# HH-08MX.net
KiCad netlist of a schematic drawn in EAGLE
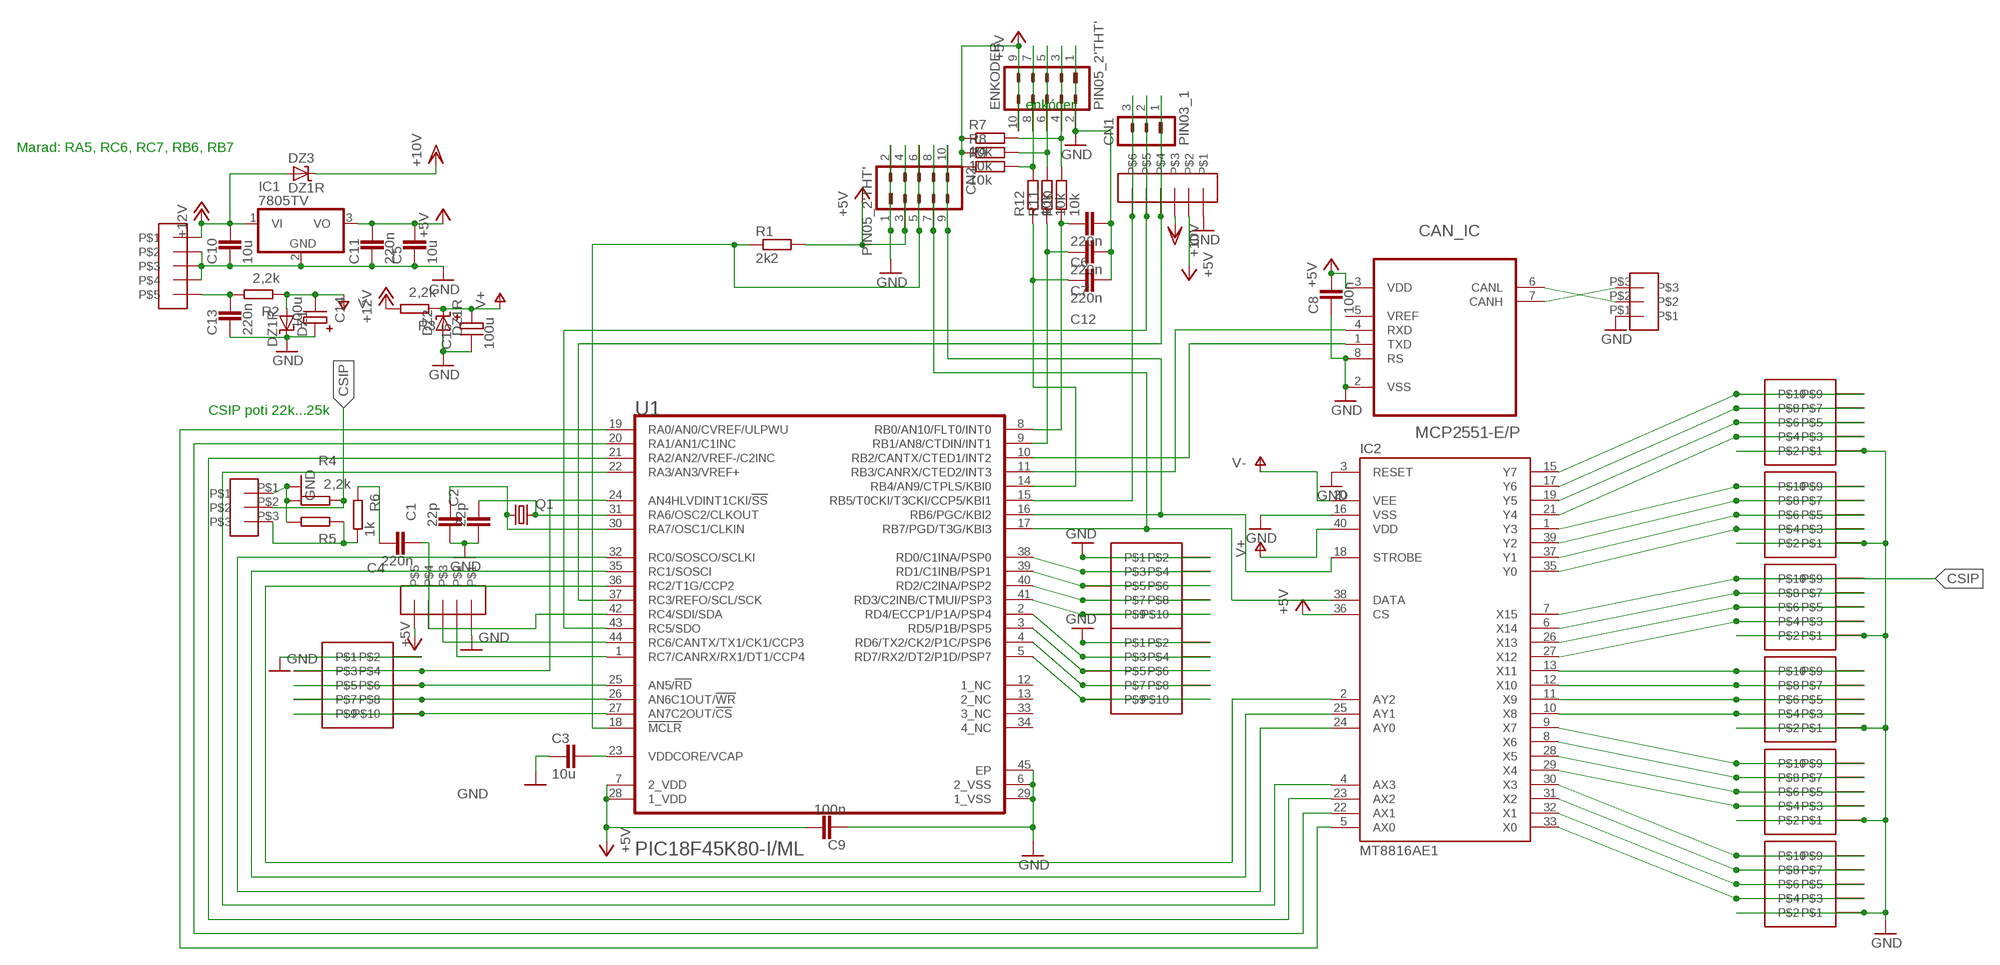
[diagram p0: schematic, sheet 1]

(export (version "E")
  (design (tool "Eeschema 10.0.6"))
  (components
    (comp (ref "BE1-4")
      (value "KERETES_TUS_10")
      (footprint "eagle-import:KERETES_TUS_10")
      (libsource (lib "eagle-import") (part "KERETES_TUS_10"))
    )
    (comp (ref "BE5-8")
      (value "KERETES_TUS_10")
      (footprint "eagle-import:KERETES_TUS_10")
      (libsource (lib "eagle-import") (part "KERETES_TUS_10"))
    )
    (comp (ref "BE9-12")
      (value "KERETES_TUS_10")
      (footprint "eagle-import:KERETES_TUS_10")
      (libsource (lib "eagle-import") (part "KERETES_TUS_10"))
    )
    (comp (ref "BE13-16")
      (value "KERETES_TUS_10")
      (footprint "eagle-import:KERETES_TUS_10")
      (libsource (lib "eagle-import") (part "KERETES_TUS_10"))
    )
    (comp (ref "C1")
      (value "22p")
      (footprint "eagle-import:R_0805_NAGY")
      (libsource (lib "eagle-import") (part "C0805_NAGY"))
    )
    (comp (ref "C2")
      (value "22p")
      (footprint "eagle-import:R_0805_NAGY")
      (libsource (lib "eagle-import") (part "C0805_NAGY"))
    )
    (comp (ref "C3")
      (value "10u")
      (footprint "eagle-import:R_0805_NAGY")
      (libsource (lib "eagle-import") (part "C0805_NAGY"))
    )
    (comp (ref "C4")
      (value "220n")
      (footprint "eagle-import:R_0805_NAGY")
      (libsource (lib "eagle-import") (part "C0805_NAGY"))
    )
    (comp (ref "C5")
      (value "10u")
      (footprint "eagle-import:R_0805_NAGY")
      (libsource (lib "eagle-import") (part "C0805_NAGY"))
    )
    (comp (ref "C6")
      (value "220n")
      (footprint "eagle-import:R_0805_NAGY")
      (libsource (lib "eagle-import") (part "C0805_NAGY"))
    )
    (comp (ref "C7")
      (value "220n")
      (footprint "eagle-import:R_0805_NAGY")
      (libsource (lib "eagle-import") (part "C0805_NAGY"))
    )
    (comp (ref "C8")
      (value "100n")
      (footprint "eagle-import:R_0805_NAGY")
      (libsource (lib "eagle-import") (part "C0805_NAGY"))
    )
    (comp (ref "C9")
      (value "100n")
      (footprint "eagle-import:R_0805_NAGY")
      (libsource (lib "eagle-import") (part "C0805_NAGY"))
    )
    (comp (ref "C10")
      (value "10u")
      (footprint "eagle-import:R_0805_NAGY")
      (libsource (lib "eagle-import") (part "C0805_NAGY"))
    )
    (comp (ref "C11")
      (value "220n")
      (footprint "eagle-import:R_0805_NAGY")
      (libsource (lib "eagle-import") (part "C0805_NAGY"))
    )
    (comp (ref "C12")
      (value "220n")
      (footprint "eagle-import:R_0805_NAGY")
      (libsource (lib "eagle-import") (part "C0805_NAGY"))
    )
    (comp (ref "C13")
      (value "220n")
      (footprint "eagle-import:R_0805_NAGY")
      (libsource (lib "eagle-import") (part "C0805_NAGY"))
    )
    (comp (ref "C14")
      (value "100u")
      (footprint "eagle-import:C_EL1RASZT06")
      (libsource (lib "eagle-import") (part "C_EL1R06"))
    )
    (comp (ref "C15")
      (value "100u")
      (footprint "eagle-import:C_EL1RASZT06")
      (libsource (lib "eagle-import") (part "C_EL1R06"))
    )
    (comp (ref "CAN_IC")
      (value "MCP2551-E/P")
      (footprint "eagle-import:DIP254P762X432-8")
      (libsource (lib "eagle-import") (part "MCP2551-E/P"))
    )
    (comp (ref "CN1")
      (value "PIN03_1")
      (footprint "eagle-import:PIN03_1")
      (libsource (lib "eagle-import") (part "PIN03_1"))
    )
    (comp (ref "CN2")
      (value "PIN05_2'THT'")
      (footprint "eagle-import:PIN05_2")
      (libsource (lib "eagle-import") (part "PIN05_2'THT'"))
    )
    (comp (ref "DZ1")
      (value "DZ1R")
      (footprint "eagle-import:D1RASZT")
      (libsource (lib "eagle-import") (part "DZ1R"))
    )
    (comp (ref "DZ2")
      (value "DZ1R")
      (footprint "eagle-import:D1RASZT")
      (libsource (lib "eagle-import") (part "DZ1R"))
    )
    (comp (ref "DZ3")
      (value "DZ1R")
      (footprint "eagle-import:D1RASZT")
      (libsource (lib "eagle-import") (part "DZ1R"))
    )
    (comp (ref "ENKODER")
      (value "PIN05_2'THT'")
      (footprint "eagle-import:PIN05_2")
      (libsource (lib "eagle-import") (part "PIN05_2'THT'"))
    )
    (comp (ref "IC1")
      (value "7805TV")
      (footprint "eagle-import:TO220V")
      (libsource (lib "eagle-import") (part "78TV05"))
    )
    (comp (ref "IC2")
      (value "MT8816AE1")
      (footprint "eagle-import:DIL40")
      (libsource (lib "eagle-import") (part "MT8816AE1"))
    )
    (comp (ref "KI1-4")
      (value "KERETES_TUS_10")
      (footprint "eagle-import:KERETES_TUS_10")
      (libsource (lib "eagle-import") (part "KERETES_TUS_10"))
    )
    (comp (ref "KI5-8")
      (value "KERETES_TUS_10")
      (footprint "eagle-import:KERETES_TUS_10")
      (libsource (lib "eagle-import") (part "KERETES_TUS_10"))
    )
    (comp (ref "KIJELZO")
      (value "FEHER_TUS_6")
      (footprint "eagle-import:FEHER_TUS_6")
      (libsource (lib "eagle-import") (part "FEHER_TUS_6"))
    )
    (comp (ref "Q1")
      (value "XTAL_2QS")
      (footprint "eagle-import:XTAL_QS")
      (libsource (lib "eagle-import") (part "XTAL_2QS"))
    )
    (comp (ref "R1")
      (value "2k2")
      (footprint "eagle-import:R0805")
      (libsource (lib "eagle-import") (part "R-EU_R0805"))
    )
    (comp (ref "R2")
      (value "2,2k")
      (footprint "eagle-import:R_0805_NAGY")
      (libsource (lib "eagle-import") (part "R_EU0805_NAGY"))
    )
    (comp (ref "R3")
      (value "2,2k")
      (footprint "eagle-import:R_0805_NAGY")
      (libsource (lib "eagle-import") (part "R_EU0805_NAGY"))
    )
    (comp (ref "R4")
      (value "2,2k")
      (footprint "eagle-import:R_0805_NAGY")
      (libsource (lib "eagle-import") (part "R_EU0805_NAGY"))
    )
    (comp (ref "R5")
      (value "R_EU0805_NAGY")
      (footprint "eagle-import:R_0805_NAGY")
      (libsource (lib "eagle-import") (part "R_EU0805_NAGY"))
    )
    (comp (ref "R6")
      (value "1k")
      (footprint "eagle-import:R_0805_NAGY")
      (libsource (lib "eagle-import") (part "R_EU0805_NAGY"))
    )
    (comp (ref "R7")
      (value "10k")
      (footprint "eagle-import:R0805")
      (libsource (lib "eagle-import") (part "R-EU_R0805"))
    )
    (comp (ref "R8")
      (value "10k")
      (footprint "eagle-import:R0805")
      (libsource (lib "eagle-import") (part "R-EU_R0805"))
    )
    (comp (ref "R9")
      (value "10k")
      (footprint "eagle-import:R0805")
      (libsource (lib "eagle-import") (part "R-EU_R0805"))
    )
    (comp (ref "R10")
      (value "10k")
      (footprint "eagle-import:R0805")
      (libsource (lib "eagle-import") (part "R-EU_R0805"))
    )
    (comp (ref "R11")
      (value "10k")
      (footprint "eagle-import:R0805")
      (libsource (lib "eagle-import") (part "R-EU_R0805"))
    )
    (comp (ref "R12")
      (value "10k")
      (footprint "eagle-import:R0805")
      (libsource (lib "eagle-import") (part "R-EU_R0805"))
    )
    (comp (ref "SOROSPORT")
      (value "FEHER_TUS_5")
      (footprint "eagle-import:FEHER_TUS_5")
      (libsource (lib "eagle-import") (part "FEHER_TUS_5"))
    )
    (comp (ref "U$1")
      (value "FEHER_TUS_3")
      (footprint "eagle-import:FEHER_TUS_3")
      (libsource (lib "eagle-import") (part "FEHER_TUS_3"))
    )
    (comp (ref "U$4")
      (value "FEHER_TUS_3")
      (footprint "eagle-import:FEHER_TUS_3")
      (libsource (lib "eagle-import") (part "FEHER_TUS_3"))
    )
    (comp (ref "U$5")
      (value "FEHER_TUS_5")
      (footprint "eagle-import:FEHER_TUS_5")
      (libsource (lib "eagle-import") (part "FEHER_TUS_5"))
    )
    (comp (ref "U$14")
      (value "KERETES_TUS_10")
      (footprint "eagle-import:KERETES_TUS_10")
      (libsource (lib "eagle-import") (part "KERETES_TUS_10"))
    )
    (comp (ref "U$15")
      (value "KERETES_TUS_10")
      (footprint "eagle-import:KERETES_TUS_10")
      (libsource (lib "eagle-import") (part "KERETES_TUS_10"))
    )
    (comp (ref "U$16")
      (value "KERETES_TUS_10")
      (footprint "eagle-import:KERETES_TUS_10")
      (libsource (lib "eagle-import") (part "KERETES_TUS_10"))
    )
    (comp (ref "U1")
      (value "MICROCHIP_PIC18F45K80-I-MLMICROCHIP_PIC18F45K80-I-ML_0_2")
      (footprint "eagle-import:MICROCHIP_PIC18F45K80-I-ML_2")
      (fields (field (name "MF") "Microchip") (field (name "MPN") "PIC18F45K80-I/ML"))
      (libsource (lib "eagle-import") (part "MICROCHIP_PIC18F45K80-I-MLMICROCHIP_PIC18F45K80-I-ML_0_2"))
    )
  )
  (nets
    (net (code "1") (name "+5V") (class "Default")
      (node (ref "C11") (pin "1") (pinfunction "1_1") (pintype "passive"))
      (node (ref "C5") (pin "1") (pinfunction "1_1") (pintype "passive"))
      (node (ref "C8") (pin "1") (pinfunction "1_1") (pintype "passive"))
      (node (ref "C9") (pin "1") (pinfunction "1_1") (pintype "passive"))
      (node (ref "CAN_IC") (pin "3") (pinfunction "VDD_3") (pintype "power_in"))
      (node (ref "CN2") (pin "3") (pinfunction "3_3") (pintype "passive"))
      (node (ref "CN2") (pin "4") (pinfunction "4_4") (pintype "passive"))
      (node (ref "ENKODER") (pin "10") (pinfunction "10_10") (pintype "passive"))
      (node (ref "ENKODER") (pin "9") (pinfunction "9_9") (pintype "passive"))
      (node (ref "IC1") (pin "3") (pinfunction "VO_3") (pintype "passive"))
      (node (ref "IC2") (pin "36") (pinfunction "CS_36") (pintype "input"))
      (node (ref "KIJELZO") (pin "P$2") (pinfunction "P$2_P$2") (pintype "bidirectional"))
      (node (ref "R1") (pin "2") (pinfunction "2_2") (pintype "passive"))
      (node (ref "R7") (pin "1") (pinfunction "1_1") (pintype "passive"))
      (node (ref "R8") (pin "1") (pinfunction "1_1") (pintype "passive"))
      (node (ref "R9") (pin "1") (pinfunction "1_1") (pintype "passive"))
      (node (ref "SOROSPORT") (pin "P$5") (pinfunction "P$5_P$5") (pintype "bidirectional"))
      (node (ref "U1") (pin "28") (pinfunction "1_VDD_28") (pintype "power_in"))
      (node (ref "U1") (pin "7") (pinfunction "2_VDD_7") (pintype "power_in"))
    )
    (net (code "2") (name "+10V") (class "Default")
      (node (ref "DZ3") (pin "P$2") (pinfunction "C_P$2") (pintype "passive"))
      (node (ref "KIJELZO") (pin "P$3") (pinfunction "P$3_P$3") (pintype "bidirectional"))
    )
    (net (code "3") (name "+12V") (class "Default")
      (node (ref "C10") (pin "1") (pinfunction "1_1") (pintype "passive"))
      (node (ref "DZ3") (pin "P$1") (pinfunction "A_P$1") (pintype "passive"))
      (node (ref "IC1") (pin "1") (pinfunction "VI_1") (pintype "input"))
      (node (ref "R3") (pin "2") (pinfunction "E_2") (pintype "passive"))
      (node (ref "U$5") (pin "P$1") (pinfunction "P$1_P$1") (pintype "bidirectional"))
    )
    (net (code "4") (name "CSIP") (class "Default")
      (node (ref "BE13-16") (pin "P$10") (pinfunction "P$10_P$10") (pintype "bidirectional"))
      (node (ref "BE13-16") (pin "P$9") (pinfunction "P$9_P$9") (pintype "bidirectional"))
      (node (ref "IC2") (pin "7") (pinfunction "X15_7") (pintype "bidirectional"))
      (node (ref "R4") (pin "1") (pinfunction "A_1") (pintype "passive"))
      (node (ref "U$1") (pin "P$2") (pinfunction "P$2_P$2") (pintype "bidirectional"))
    )
    (net (code "5") (name "GND") (class "Default")
      (node (ref "BE1-4") (pin "P$1") (pinfunction "P$1_P$1") (pintype "bidirectional"))
      (node (ref "BE1-4") (pin "P$2") (pinfunction "P$2_P$2") (pintype "bidirectional"))
      (node (ref "BE13-16") (pin "P$1") (pinfunction "P$1_P$1") (pintype "bidirectional"))
      (node (ref "BE13-16") (pin "P$2") (pinfunction "P$2_P$2") (pintype "bidirectional"))
      (node (ref "BE5-8") (pin "P$1") (pinfunction "P$1_P$1") (pintype "bidirectional"))
      (node (ref "BE5-8") (pin "P$2") (pinfunction "P$2_P$2") (pintype "bidirectional"))
      (node (ref "BE9-12") (pin "P$1") (pinfunction "P$1_P$1") (pintype "bidirectional"))
      (node (ref "BE9-12") (pin "P$2") (pinfunction "P$2_P$2") (pintype "bidirectional"))
      (node (ref "C1") (pin "1") (pinfunction "1_1") (pintype "passive"))
      (node (ref "C10") (pin "2") (pinfunction "2_2") (pintype "passive"))
      (node (ref "C11") (pin "2") (pinfunction "2_2") (pintype "passive"))
      (node (ref "C12") (pin "1") (pinfunction "1_1") (pintype "passive"))
      (node (ref "C13") (pin "2") (pinfunction "2_2") (pintype "passive"))
      (node (ref "C14") (pin "P+") (pinfunction "P+_P+") (pintype "passive"))
      (node (ref "C15") (pin "P-") (pinfunction "P-_P-") (pintype "passive"))
      (node (ref "C2") (pin "1") (pinfunction "1_1") (pintype "passive"))
      (node (ref "C3") (pin "2") (pinfunction "2_2") (pintype "passive"))
      (node (ref "C5") (pin "2") (pinfunction "2_2") (pintype "passive"))
      (node (ref "C6") (pin "1") (pinfunction "1_1") (pintype "passive"))
      (node (ref "C7") (pin "1") (pinfunction "1_1") (pintype "passive"))
      (node (ref "C8") (pin "2") (pinfunction "2_2") (pintype "passive"))
      (node (ref "C9") (pin "2") (pinfunction "2_2") (pintype "passive"))
      (node (ref "CAN_IC") (pin "2") (pinfunction "VSS_2") (pintype "passive"))
      (node (ref "CAN_IC") (pin "8") (pinfunction "RS_8") (pintype "input"))
      (node (ref "CN2") (pin "1") (pinfunction "1_1") (pintype "passive"))
      (node (ref "CN2") (pin "2") (pinfunction "2_2") (pintype "passive"))
      (node (ref "DZ1") (pin "P$2") (pinfunction "C_P$2") (pintype "passive"))
      (node (ref "DZ2") (pin "P$1") (pinfunction "A_P$1") (pintype "passive"))
      (node (ref "ENKODER") (pin "1") (pinfunction "1_1") (pintype "passive"))
      (node (ref "ENKODER") (pin "2") (pinfunction "2_2") (pintype "passive"))
      (node (ref "IC1") (pin "2") (pinfunction "GND_2") (pintype "passive"))
      (node (ref "IC2") (pin "16") (pinfunction "VSS_16") (pintype "power_in"))
      (node (ref "IC2") (pin "3") (pinfunction "RESET_3") (pintype "input"))
      (node (ref "KI1-4") (pin "P$1") (pinfunction "P$1_P$1") (pintype "bidirectional"))
      (node (ref "KI1-4") (pin "P$2") (pinfunction "P$2_P$2") (pintype "bidirectional"))
      (node (ref "KI5-8") (pin "P$1") (pinfunction "P$1_P$1") (pintype "bidirectional"))
      (node (ref "KI5-8") (pin "P$2") (pinfunction "P$2_P$2") (pintype "bidirectional"))
      (node (ref "KIJELZO") (pin "P$1") (pinfunction "P$1_P$1") (pintype "bidirectional"))
      (node (ref "R4") (pin "2") (pinfunction "E_2") (pintype "passive"))
      (node (ref "R5") (pin "2") (pinfunction "E_2") (pintype "passive"))
      (node (ref "SOROSPORT") (pin "P$1") (pinfunction "P$1_P$1") (pintype "bidirectional"))
      (node (ref "U$1") (pin "P$1") (pinfunction "P$1_P$1") (pintype "bidirectional"))
      (node (ref "U$14") (pin "P$1") (pinfunction "P$1_P$1") (pintype "bidirectional"))
      (node (ref "U$14") (pin "P$2") (pinfunction "P$2_P$2") (pintype "bidirectional"))
      (node (ref "U$15") (pin "P$1") (pinfunction "P$1_P$1") (pintype "bidirectional"))
      (node (ref "U$15") (pin "P$2") (pinfunction "P$2_P$2") (pintype "bidirectional"))
      (node (ref "U$16") (pin "P$1") (pinfunction "P$1_P$1") (pintype "bidirectional"))
      (node (ref "U$16") (pin "P$2") (pinfunction "P$2_P$2") (pintype "bidirectional"))
      (node (ref "U$4") (pin "P$1") (pinfunction "P$1_P$1") (pintype "bidirectional"))
      (node (ref "U$5") (pin "P$2") (pinfunction "P$2_P$2") (pintype "bidirectional"))
      (node (ref "U$5") (pin "P$3") (pinfunction "P$3_P$3") (pintype "bidirectional"))
      (node (ref "U$5") (pin "P$4") (pinfunction "P$4_P$4") (pintype "bidirectional"))
      (node (ref "U1") (pin "29") (pinfunction "1_VSS_29") (pintype "power_in"))
      (node (ref "U1") (pin "45") (pinfunction "EP_45") (pintype "power_in"))
      (node (ref "U1") (pin "6") (pinfunction "2_VSS_6") (pintype "power_in"))
    )
    (net (code "6") (name "Net-(CAN_IC-CANH)") (class "Default")
      (node (ref "CAN_IC") (pin "7") (pinfunction "CANH_7") (pintype "output"))
      (node (ref "U$4") (pin "P$3") (pinfunction "P$3_P$3") (pintype "bidirectional"))
    )
    (net (code "7") (name "Net-(CAN_IC-CANL)") (class "Default")
      (node (ref "CAN_IC") (pin "6") (pinfunction "CANL_6") (pintype "output"))
      (node (ref "U$4") (pin "P$2") (pinfunction "P$2_P$2") (pintype "bidirectional"))
    )
    (net (code "8") (name "Net-(CAN_IC-RXD)") (class "Default")
      (node (ref "CAN_IC") (pin "4") (pinfunction "RXD_4") (pintype "input"))
      (node (ref "U1") (pin "11") (pinfunction "RB3/CANRX/CTED2/INT3_11") (pintype "bidirectional"))
    )
    (net (code "9") (name "Net-(CAN_IC-TXD)") (class "Default")
      (node (ref "CAN_IC") (pin "1") (pinfunction "TXD_1") (pintype "input"))
      (node (ref "U1") (pin "10") (pinfunction "RB2/CANTX/CTED1/INT2_10") (pintype "bidirectional"))
    )
    (net (code "10") (name "Net-(ENKODER-Pad3)") (class "Default")
      (node (ref "ENKODER") (pin "3") (pinfunction "3_3") (pintype "passive"))
      (node (ref "ENKODER") (pin "4") (pinfunction "4_4") (pintype "passive"))
      (node (ref "R10") (pin "2") (pinfunction "2_2") (pintype "passive"))
      (node (ref "R7") (pin "2") (pinfunction "2_2") (pintype "passive"))
    )
    (net (code "11") (name "Net-(ENKODER-Pad5)") (class "Default")
      (node (ref "ENKODER") (pin "5") (pinfunction "5_5") (pintype "passive"))
      (node (ref "ENKODER") (pin "6") (pinfunction "6_6") (pintype "passive"))
      (node (ref "R11") (pin "2") (pinfunction "2_2") (pintype "passive"))
      (node (ref "R8") (pin "2") (pinfunction "2_2") (pintype "passive"))
    )
    (net (code "12") (name "Net-(ENKODER-Pad7)") (class "Default")
      (node (ref "ENKODER") (pin "7") (pinfunction "7_7") (pintype "passive"))
      (node (ref "ENKODER") (pin "8") (pinfunction "8_8") (pintype "passive"))
      (node (ref "R12") (pin "2") (pinfunction "2_2") (pintype "passive"))
      (node (ref "R9") (pin "2") (pinfunction "2_2") (pintype "passive"))
    )
    (net (code "13") (name "Net-(IC2-AX0)") (class "Default")
      (node (ref "IC2") (pin "5") (pinfunction "AX0_5") (pintype "input"))
      (node (ref "U1") (pin "19") (pinfunction "RA0/AN0/CVREF/ULPWU_19") (pintype "bidirectional"))
    )
    (net (code "14") (name "Net-(IC2-AX1)") (class "Default")
      (node (ref "IC2") (pin "22") (pinfunction "AX1_22") (pintype "input"))
      (node (ref "U1") (pin "20") (pinfunction "RA1/AN1/C1INC_20") (pintype "bidirectional"))
    )
    (net (code "15") (name "Net-(IC2-AX2)") (class "Default")
      (node (ref "IC2") (pin "23") (pinfunction "AX2_23") (pintype "input"))
      (node (ref "U1") (pin "21") (pinfunction "RA2/AN2/VREF-/C2INC_21") (pintype "bidirectional"))
    )
    (net (code "16") (name "Net-(IC2-AX3)") (class "Default")
      (node (ref "IC2") (pin "4") (pinfunction "AX3_4") (pintype "input"))
      (node (ref "U1") (pin "22") (pinfunction "RA3/AN3/VREF+_22") (pintype "bidirectional"))
    )
    (net (code "17") (name "Net-(IC2-AY0)") (class "Default")
      (node (ref "IC2") (pin "24") (pinfunction "AY0_24") (pintype "input"))
      (node (ref "U1") (pin "32") (pinfunction "RC0/SOSCO/SCLKI_32") (pintype "bidirectional"))
    )
    (net (code "18") (name "Net-(IC2-AY1)") (class "Default")
      (node (ref "IC2") (pin "25") (pinfunction "AY1_25") (pintype "input"))
      (node (ref "U1") (pin "35") (pinfunction "RC1/SOSCI_35") (pintype "bidirectional"))
    )
    (net (code "19") (name "Net-(IC2-AY2)") (class "Default")
      (node (ref "IC2") (pin "2") (pinfunction "AY2_2") (pintype "input"))
      (node (ref "U1") (pin "36") (pinfunction "RC2/T1G/CCP2_36") (pintype "bidirectional"))
    )
    (net (code "20") (name "Net-(IC2-DATA)") (class "Default")
      (node (ref "CN2") (pin "7") (pinfunction "7_7") (pintype "passive"))
      (node (ref "CN2") (pin "8") (pinfunction "8_8") (pintype "passive"))
      (node (ref "IC2") (pin "38") (pinfunction "DATA_38") (pintype "input"))
      (node (ref "U1") (pin "17") (pinfunction "RB7/PGD/T3G/KBI3_17") (pintype "bidirectional"))
    )
    (net (code "21") (name "Net-(IC2-STROBE)") (class "Default")
      (node (ref "CN2") (pin "10") (pinfunction "10_10") (pintype "passive"))
      (node (ref "CN2") (pin "9") (pinfunction "9_9") (pintype "passive"))
      (node (ref "IC2") (pin "18") (pinfunction "STROBE_18") (pintype "input"))
      (node (ref "U1") (pin "16") (pinfunction "RB6/PGC/KBI2_16") (pintype "bidirectional"))
    )
    (net (code "22") (name "Net-(IC2-X0)") (class "Default")
      (node (ref "BE1-4") (pin "P$3") (pinfunction "P$3_P$3") (pintype "bidirectional"))
      (node (ref "BE1-4") (pin "P$4") (pinfunction "P$4_P$4") (pintype "bidirectional"))
      (node (ref "IC2") (pin "33") (pinfunction "X0_33") (pintype "bidirectional"))
    )
    (net (code "23") (name "Net-(IC2-X1)") (class "Default")
      (node (ref "BE1-4") (pin "P$5") (pinfunction "P$5_P$5") (pintype "bidirectional"))
      (node (ref "BE1-4") (pin "P$6") (pinfunction "P$6_P$6") (pintype "bidirectional"))
      (node (ref "IC2") (pin "32") (pinfunction "X1_32") (pintype "bidirectional"))
    )
    (net (code "24") (name "Net-(IC2-X2)") (class "Default")
      (node (ref "BE1-4") (pin "P$7") (pinfunction "P$7_P$7") (pintype "bidirectional"))
      (node (ref "BE1-4") (pin "P$8") (pinfunction "P$8_P$8") (pintype "bidirectional"))
      (node (ref "IC2") (pin "31") (pinfunction "X2_31") (pintype "bidirectional"))
    )
    (net (code "25") (name "Net-(IC2-X3)") (class "Default")
      (node (ref "BE1-4") (pin "P$10") (pinfunction "P$10_P$10") (pintype "bidirectional"))
      (node (ref "BE1-4") (pin "P$9") (pinfunction "P$9_P$9") (pintype "bidirectional"))
      (node (ref "IC2") (pin "30") (pinfunction "X3_30") (pintype "bidirectional"))
    )
    (net (code "26") (name "Net-(IC2-X4)") (class "Default")
      (node (ref "BE5-8") (pin "P$3") (pinfunction "P$3_P$3") (pintype "bidirectional"))
      (node (ref "BE5-8") (pin "P$4") (pinfunction "P$4_P$4") (pintype "bidirectional"))
      (node (ref "IC2") (pin "29") (pinfunction "X4_29") (pintype "bidirectional"))
    )
    (net (code "27") (name "Net-(IC2-X5)") (class "Default")
      (node (ref "BE5-8") (pin "P$5") (pinfunction "P$5_P$5") (pintype "bidirectional"))
      (node (ref "BE5-8") (pin "P$6") (pinfunction "P$6_P$6") (pintype "bidirectional"))
      (node (ref "IC2") (pin "28") (pinfunction "X5_28") (pintype "bidirectional"))
    )
    (net (code "28") (name "Net-(IC2-X6)") (class "Default")
      (node (ref "BE5-8") (pin "P$7") (pinfunction "P$7_P$7") (pintype "bidirectional"))
      (node (ref "BE5-8") (pin "P$8") (pinfunction "P$8_P$8") (pintype "bidirectional"))
      (node (ref "IC2") (pin "8") (pinfunction "X6_8") (pintype "bidirectional"))
    )
    (net (code "29") (name "Net-(IC2-X7)") (class "Default")
      (node (ref "BE5-8") (pin "P$10") (pinfunction "P$10_P$10") (pintype "bidirectional"))
      (node (ref "BE5-8") (pin "P$9") (pinfunction "P$9_P$9") (pintype "bidirectional"))
      (node (ref "IC2") (pin "9") (pinfunction "X7_9") (pintype "bidirectional"))
    )
    (net (code "30") (name "Net-(IC2-X8)") (class "Default")
      (node (ref "BE9-12") (pin "P$3") (pinfunction "P$3_P$3") (pintype "bidirectional"))
      (node (ref "BE9-12") (pin "P$4") (pinfunction "P$4_P$4") (pintype "bidirectional"))
      (node (ref "IC2") (pin "10") (pinfunction "X8_10") (pintype "bidirectional"))
    )
    (net (code "31") (name "Net-(IC2-X9)") (class "Default")
      (node (ref "BE9-12") (pin "P$5") (pinfunction "P$5_P$5") (pintype "bidirectional"))
      (node (ref "BE9-12") (pin "P$6") (pinfunction "P$6_P$6") (pintype "bidirectional"))
      (node (ref "IC2") (pin "11") (pinfunction "X9_11") (pintype "bidirectional"))
    )
    (net (code "32") (name "Net-(IC2-X10)") (class "Default")
      (node (ref "BE9-12") (pin "P$7") (pinfunction "P$7_P$7") (pintype "bidirectional"))
      (node (ref "BE9-12") (pin "P$8") (pinfunction "P$8_P$8") (pintype "bidirectional"))
      (node (ref "IC2") (pin "12") (pinfunction "X10_12") (pintype "bidirectional"))
    )
    (net (code "33") (name "Net-(IC2-X11)") (class "Default")
      (node (ref "BE9-12") (pin "P$10") (pinfunction "P$10_P$10") (pintype "bidirectional"))
      (node (ref "BE9-12") (pin "P$9") (pinfunction "P$9_P$9") (pintype "bidirectional"))
      (node (ref "IC2") (pin "13") (pinfunction "X11_13") (pintype "bidirectional"))
    )
    (net (code "34") (name "Net-(IC2-X12)") (class "Default")
      (node (ref "BE13-16") (pin "P$3") (pinfunction "P$3_P$3") (pintype "bidirectional"))
      (node (ref "BE13-16") (pin "P$4") (pinfunction "P$4_P$4") (pintype "bidirectional"))
      (node (ref "IC2") (pin "27") (pinfunction "X12_27") (pintype "bidirectional"))
    )
    (net (code "35") (name "Net-(IC2-X13)") (class "Default")
      (node (ref "BE13-16") (pin "P$5") (pinfunction "P$5_P$5") (pintype "bidirectional"))
      (node (ref "BE13-16") (pin "P$6") (pinfunction "P$6_P$6") (pintype "bidirectional"))
      (node (ref "IC2") (pin "26") (pinfunction "X13_26") (pintype "bidirectional"))
    )
    (net (code "36") (name "Net-(IC2-X14)") (class "Default")
      (node (ref "BE13-16") (pin "P$7") (pinfunction "P$7_P$7") (pintype "bidirectional"))
      (node (ref "BE13-16") (pin "P$8") (pinfunction "P$8_P$8") (pintype "bidirectional"))
      (node (ref "IC2") (pin "6") (pinfunction "X14_6") (pintype "bidirectional"))
    )
    (net (code "37") (name "Net-(IC2-Y0)") (class "Default")
      (node (ref "IC2") (pin "35") (pinfunction "Y0_35") (pintype "bidirectional"))
      (node (ref "KI1-4") (pin "P$3") (pinfunction "P$3_P$3") (pintype "bidirectional"))
      (node (ref "KI1-4") (pin "P$4") (pinfunction "P$4_P$4") (pintype "bidirectional"))
    )
    (net (code "38") (name "Net-(IC2-Y1)") (class "Default")
      (node (ref "IC2") (pin "37") (pinfunction "Y1_37") (pintype "bidirectional"))
      (node (ref "KI1-4") (pin "P$5") (pinfunction "P$5_P$5") (pintype "bidirectional"))
      (node (ref "KI1-4") (pin "P$6") (pinfunction "P$6_P$6") (pintype "bidirectional"))
    )
    (net (code "39") (name "Net-(IC2-Y2)") (class "Default")
      (node (ref "IC2") (pin "39") (pinfunction "Y2_39") (pintype "bidirectional"))
      (node (ref "KI1-4") (pin "P$7") (pinfunction "P$7_P$7") (pintype "bidirectional"))
      (node (ref "KI1-4") (pin "P$8") (pinfunction "P$8_P$8") (pintype "bidirectional"))
    )
    (net (code "40") (name "Net-(IC2-Y3)") (class "Default")
      (node (ref "IC2") (pin "1") (pinfunction "Y3_1") (pintype "bidirectional"))
      (node (ref "KI1-4") (pin "P$10") (pinfunction "P$10_P$10") (pintype "bidirectional"))
      (node (ref "KI1-4") (pin "P$9") (pinfunction "P$9_P$9") (pintype "bidirectional"))
    )
    (net (code "41") (name "Net-(IC2-Y4)") (class "Default")
      (node (ref "IC2") (pin "21") (pinfunction "Y4_21") (pintype "bidirectional"))
      (node (ref "KI5-8") (pin "P$3") (pinfunction "P$3_P$3") (pintype "bidirectional"))
      (node (ref "KI5-8") (pin "P$4") (pinfunction "P$4_P$4") (pintype "bidirectional"))
    )
    (net (code "42") (name "Net-(IC2-Y5)") (class "Default")
      (node (ref "IC2") (pin "19") (pinfunction "Y5_19") (pintype "bidirectional"))
      (node (ref "KI5-8") (pin "P$5") (pinfunction "P$5_P$5") (pintype "bidirectional"))
      (node (ref "KI5-8") (pin "P$6") (pinfunction "P$6_P$6") (pintype "bidirectional"))
    )
    (net (code "43") (name "Net-(IC2-Y6)") (class "Default")
      (node (ref "IC2") (pin "17") (pinfunction "Y6_17") (pintype "bidirectional"))
      (node (ref "KI5-8") (pin "P$7") (pinfunction "P$7_P$7") (pintype "bidirectional"))
      (node (ref "KI5-8") (pin "P$8") (pinfunction "P$8_P$8") (pintype "bidirectional"))
    )
    (net (code "44") (name "Net-(IC2-Y7)") (class "Default")
      (node (ref "IC2") (pin "15") (pinfunction "Y7_15") (pintype "bidirectional"))
      (node (ref "KI5-8") (pin "P$10") (pinfunction "P$10_P$10") (pintype "bidirectional"))
      (node (ref "KI5-8") (pin "P$9") (pinfunction "P$9_P$9") (pintype "bidirectional"))
    )
    (net (code "45") (name "Net-(R2-E)") (class "Default")
      (node (ref "C13") (pin "1") (pinfunction "1_1") (pintype "passive"))
      (node (ref "R2") (pin "2") (pinfunction "E_2") (pintype "passive"))
      (node (ref "U$5") (pin "P$5") (pinfunction "P$5_P$5") (pintype "bidirectional"))
    )
    (net (code "46") (name "Net-(R5-A)") (class "Default")
      (node (ref "R5") (pin "1") (pinfunction "A_1") (pintype "passive"))
      (node (ref "R6") (pin "2") (pinfunction "E_2") (pintype "passive"))
      (node (ref "U$1") (pin "P$3") (pinfunction "P$3_P$3") (pintype "bidirectional"))
    )
    (net (code "47") (name "Net-(R6-A)") (class "Default")
      (node (ref "C4") (pin "2") (pinfunction "2_2") (pintype "passive"))
      (node (ref "R6") (pin "1") (pinfunction "A_1") (pintype "passive"))
    )
    (net (code "48") (name "Net-(U1-AN4HLVDINT1CKI{slash}~{SS})") (class "Default")
      (node (ref "U$16") (pin "P$3") (pinfunction "P$3_P$3") (pintype "bidirectional"))
      (node (ref "U$16") (pin "P$4") (pinfunction "P$4_P$4") (pintype "bidirectional"))
      (node (ref "U1") (pin "24") (pinfunction "AN4HLVDINT1CKI/~{SS}_24") (pintype "bidirectional"))
    )
    (net (code "49") (name "Net-(U1-AN5{slash}~{RD})") (class "Default")
      (node (ref "U$16") (pin "P$5") (pinfunction "P$5_P$5") (pintype "bidirectional"))
      (node (ref "U$16") (pin "P$6") (pinfunction "P$6_P$6") (pintype "bidirectional"))
      (node (ref "U1") (pin "25") (pinfunction "AN5/~{RD}_25") (pintype "bidirectional"))
    )
    (net (code "50") (name "Net-(U1-AN6C1OUT{slash}~{WR})") (class "Default")
      (node (ref "U$16") (pin "P$7") (pinfunction "P$7_P$7") (pintype "bidirectional"))
      (node (ref "U$16") (pin "P$8") (pinfunction "P$8_P$8") (pintype "bidirectional"))
      (node (ref "U1") (pin "26") (pinfunction "AN6C1OUT/~{WR}_26") (pintype "bidirectional"))
    )
    (net (code "51") (name "Net-(U1-AN7C2OUT{slash}~{CS})") (class "Default")
      (node (ref "U$16") (pin "P$10") (pinfunction "P$10_P$10") (pintype "bidirectional"))
      (node (ref "U$16") (pin "P$9") (pinfunction "P$9_P$9") (pintype "bidirectional"))
      (node (ref "U1") (pin "27") (pinfunction "AN7C2OUT/~{CS}_27") (pintype "bidirectional"))
    )
    (net (code "52") (name "Net-(U1-RA6{slash}OSC2{slash}CLKOUT)") (class "Default")
      (node (ref "C2") (pin "2") (pinfunction "2_2") (pintype "passive"))
      (node (ref "Q1") (pin "2") (pinfunction "2_2") (pintype "passive"))
      (node (ref "U1") (pin "31") (pinfunction "RA6/OSC2/CLKOUT_31") (pintype "bidirectional"))
    )
    (net (code "53") (name "Net-(U1-RA7{slash}OSC1{slash}CLKIN)") (class "Default")
      (node (ref "C1") (pin "2") (pinfunction "2_2") (pintype "passive"))
      (node (ref "Q1") (pin "1") (pinfunction "1_1") (pintype "passive"))
      (node (ref "U1") (pin "30") (pinfunction "RA7/OSC1/CLKIN_30") (pintype "bidirectional"))
    )
    (net (code "54") (name "Net-(U1-RB0{slash}AN10{slash}FLT0{slash}INT0)") (class "Default")
      (node (ref "C6") (pin "2") (pinfunction "2_2") (pintype "passive"))
      (node (ref "R10") (pin "1") (pinfunction "1_1") (pintype "passive"))
      (node (ref "U1") (pin "8") (pinfunction "RB0/AN10/FLT0/INT0_8") (pintype "bidirectional"))
    )
    (net (code "55") (name "Net-(U1-RB1{slash}AN8{slash}CTDIN{slash}INT1)") (class "Default")
      (node (ref "C7") (pin "2") (pinfunction "2_2") (pintype "passive"))
      (node (ref "R11") (pin "1") (pinfunction "1_1") (pintype "passive"))
      (node (ref "U1") (pin "9") (pinfunction "RB1/AN8/CTDIN/INT1_9") (pintype "bidirectional"))
    )
    (net (code "56") (name "Net-(U1-RB4{slash}AN9{slash}CTPLS{slash}KBI0)") (class "Default")
      (node (ref "C12") (pin "2") (pinfunction "2_2") (pintype "passive"))
      (node (ref "R12") (pin "1") (pinfunction "1_1") (pintype "passive"))
      (node (ref "U1") (pin "14") (pinfunction "RB4/AN9/CTPLS/KBI0_14") (pintype "bidirectional"))
    )
    (net (code "57") (name "Net-(U1-RB5{slash}T0CKI{slash}T3CKI{slash}CCP5{slash}KBI1)") (class "Default")
      (node (ref "CN1") (pin "3") (pinfunction "3_3") (pintype "passive"))
      (node (ref "KIJELZO") (pin "P$6") (pinfunction "P$6_P$6") (pintype "bidirectional"))
      (node (ref "U1") (pin "15") (pinfunction "RB5/T0CKI/T3CKI/CCP5/KBI1_15") (pintype "bidirectional"))
    )
    (net (code "58") (name "Net-(U1-RC3{slash}REFO{slash}SCL{slash}SCK)") (class "Default")
      (node (ref "CN1") (pin "1") (pinfunction "1_1") (pintype "passive"))
      (node (ref "KIJELZO") (pin "P$4") (pinfunction "P$4_P$4") (pintype "bidirectional"))
      (node (ref "U1") (pin "37") (pinfunction "RC3/REFO/SCL/SCK_37") (pintype "bidirectional"))
    )
    (net (code "59") (name "Net-(U1-RC4{slash}SDI{slash}SDA)") (class "Default")
      (node (ref "C4") (pin "1") (pinfunction "1_1") (pintype "passive"))
      (node (ref "SOROSPORT") (pin "P$4") (pinfunction "P$4_P$4") (pintype "bidirectional"))
      (node (ref "U1") (pin "42") (pinfunction "RC4/SDI/SDA_42") (pintype "bidirectional"))
    )
    (net (code "60") (name "Net-(U1-RC5{slash}SDO)") (class "Default")
      (node (ref "CN1") (pin "2") (pinfunction "2_2") (pintype "passive"))
      (node (ref "KIJELZO") (pin "P$5") (pinfunction "P$5_P$5") (pintype "bidirectional"))
      (node (ref "U1") (pin "43") (pinfunction "RC5/SDO_43") (pintype "bidirectional"))
    )
    (net (code "61") (name "Net-(U1-RC6{slash}CANTX{slash}TX1{slash}CK1{slash}CCP3)") (class "Default")
      (node (ref "SOROSPORT") (pin "P$3") (pinfunction "P$3_P$3") (pintype "bidirectional"))
      (node (ref "U1") (pin "44") (pinfunction "RC6/CANTX/TX1/CK1/CCP3_44") (pintype "bidirectional"))
    )
    (net (code "62") (name "Net-(U1-RC7{slash}CANRX{slash}RX1{slash}DT1{slash}CCP4)") (class "Default")
      (node (ref "SOROSPORT") (pin "P$2") (pinfunction "P$2_P$2") (pintype "bidirectional"))
      (node (ref "U1") (pin "1") (pinfunction "RC7/CANRX/RX1/DT1/CCP4_1") (pintype "bidirectional"))
    )
    (net (code "63") (name "Net-(U1-RD0{slash}C1INA{slash}PSP0)") (class "Default")
      (node (ref "U$14") (pin "P$3") (pinfunction "P$3_P$3") (pintype "bidirectional"))
      (node (ref "U$14") (pin "P$4") (pinfunction "P$4_P$4") (pintype "bidirectional"))
      (node (ref "U1") (pin "38") (pinfunction "RD0/C1INA/PSP0_38") (pintype "bidirectional"))
    )
    (net (code "64") (name "Net-(U1-RD1{slash}C1INB{slash}PSP1)") (class "Default")
      (node (ref "U$14") (pin "P$5") (pinfunction "P$5_P$5") (pintype "bidirectional"))
      (node (ref "U$14") (pin "P$6") (pinfunction "P$6_P$6") (pintype "bidirectional"))
      (node (ref "U1") (pin "39") (pinfunction "RD1/C1INB/PSP1_39") (pintype "bidirectional"))
    )
    (net (code "65") (name "Net-(U1-RD2{slash}C2INA{slash}PSP2)") (class "Default")
      (node (ref "U$14") (pin "P$7") (pinfunction "P$7_P$7") (pintype "bidirectional"))
      (node (ref "U$14") (pin "P$8") (pinfunction "P$8_P$8") (pintype "bidirectional"))
      (node (ref "U1") (pin "40") (pinfunction "RD2/C2INA/PSP2_40") (pintype "bidirectional"))
    )
    (net (code "66") (name "Net-(U1-RD3{slash}C2INB{slash}CTMUI{slash}PSP3)") (class "Default")
      (node (ref "U$14") (pin "P$10") (pinfunction "P$10_P$10") (pintype "bidirectional"))
      (node (ref "U$14") (pin "P$9") (pinfunction "P$9_P$9") (pintype "bidirectional"))
      (node (ref "U1") (pin "41") (pinfunction "RD3/C2INB/CTMUI/PSP3_41") (pintype "bidirectional"))
    )
    (net (code "67") (name "Net-(U1-RD4{slash}ECCP1{slash}P1A{slash}PSP4)") (class "Default")
      (node (ref "U$15") (pin "P$3") (pinfunction "P$3_P$3") (pintype "bidirectional"))
      (node (ref "U$15") (pin "P$4") (pinfunction "P$4_P$4") (pintype "bidirectional"))
      (node (ref "U1") (pin "2") (pinfunction "RD4/ECCP1/P1A/PSP4_2") (pintype "bidirectional"))
    )
    (net (code "68") (name "Net-(U1-RD5{slash}P1B{slash}PSP5)") (class "Default")
      (node (ref "U$15") (pin "P$5") (pinfunction "P$5_P$5") (pintype "bidirectional"))
      (node (ref "U$15") (pin "P$6") (pinfunction "P$6_P$6") (pintype "bidirectional"))
      (node (ref "U1") (pin "3") (pinfunction "RD5/P1B/PSP5_3") (pintype "bidirectional"))
    )
    (net (code "69") (name "Net-(U1-RD6{slash}TX2{slash}CK2{slash}P1C{slash}PSP6)") (class "Default")
      (node (ref "U$15") (pin "P$7") (pinfunction "P$7_P$7") (pintype "bidirectional"))
      (node (ref "U$15") (pin "P$8") (pinfunction "P$8_P$8") (pintype "bidirectional"))
      (node (ref "U1") (pin "4") (pinfunction "RD6/TX2/CK2/P1C/PSP6_4") (pintype "bidirectional"))
    )
    (net (code "70") (name "Net-(U1-RD7{slash}RX2{slash}DT2{slash}P1D{slash}PSP7)") (class "Default")
      (node (ref "U$15") (pin "P$10") (pinfunction "P$10_P$10") (pintype "bidirectional"))
      (node (ref "U$15") (pin "P$9") (pinfunction "P$9_P$9") (pintype "bidirectional"))
      (node (ref "U1") (pin "5") (pinfunction "RD7/RX2/DT2/P1D/PSP7_5") (pintype "bidirectional"))
    )
    (net (code "71") (name "Net-(U1-VDDCORE{slash}VCAP)") (class "Default")
      (node (ref "C3") (pin "1") (pinfunction "1_1") (pintype "passive"))
      (node (ref "U1") (pin "23") (pinfunction "VDDCORE/VCAP_23") (pintype "power_in"))
    )
    (net (code "72") (name "Net-(U1-~{MCLR})") (class "Default")
      (node (ref "CN2") (pin "5") (pinfunction "5_5") (pintype "passive"))
      (node (ref "CN2") (pin "6") (pinfunction "6_6") (pintype "passive"))
      (node (ref "R1") (pin "1") (pinfunction "1_1") (pintype "passive"))
      (node (ref "U1") (pin "18") (pinfunction "~{MCLR}_18") (pintype "input"))
    )
    (net (code "73") (name "V+") (class "Default")
      (node (ref "C15") (pin "P+") (pinfunction "P+_P+") (pintype "passive"))
      (node (ref "DZ2") (pin "P$2") (pinfunction "C_P$2") (pintype "passive"))
      (node (ref "IC2") (pin "40") (pinfunction "VDD_40") (pintype "power_in"))
      (node (ref "R3") (pin "1") (pinfunction "A_1") (pintype "passive"))
    )
    (net (code "74") (name "V-") (class "Default")
      (node (ref "C14") (pin "P-") (pinfunction "P-_P-") (pintype "passive"))
      (node (ref "DZ1") (pin "P$1") (pinfunction "A_P$1") (pintype "passive"))
      (node (ref "IC2") (pin "20") (pinfunction "VEE_20") (pintype "power_in"))
      (node (ref "R2") (pin "1") (pinfunction "A_1") (pintype "passive"))
    )
    (net (code "75") (name "unconnected-(CAN_IC-VREF-Pad5)") (class "Default")
      (node (ref "CAN_IC") (pin "5") (pinfunction "VREF_5") (pintype "input"))
    )
    (net (code "76") (name "unconnected-(U1-1_NC-Pad12)") (class "Default")
      (node (ref "U1") (pin "12") (pinfunction "1_NC_12") (pintype "passive"))
    )
    (net (code "77") (name "unconnected-(U1-2_NC-Pad13)") (class "Default")
      (node (ref "U1") (pin "13") (pinfunction "2_NC_13") (pintype "passive"))
    )
    (net (code "78") (name "unconnected-(U1-3_NC-Pad33)") (class "Default")
      (node (ref "U1") (pin "33") (pinfunction "3_NC_33") (pintype "passive"))
    )
    (net (code "79") (name "unconnected-(U1-4_NC-Pad34)") (class "Default")
      (node (ref "U1") (pin "34") (pinfunction "4_NC_34") (pintype "passive"))
    )
  )
)
